# PCB_Board4_schematic_2_instrument_droid.net
KiCad netlist of a schematic drawn in Altium Designer
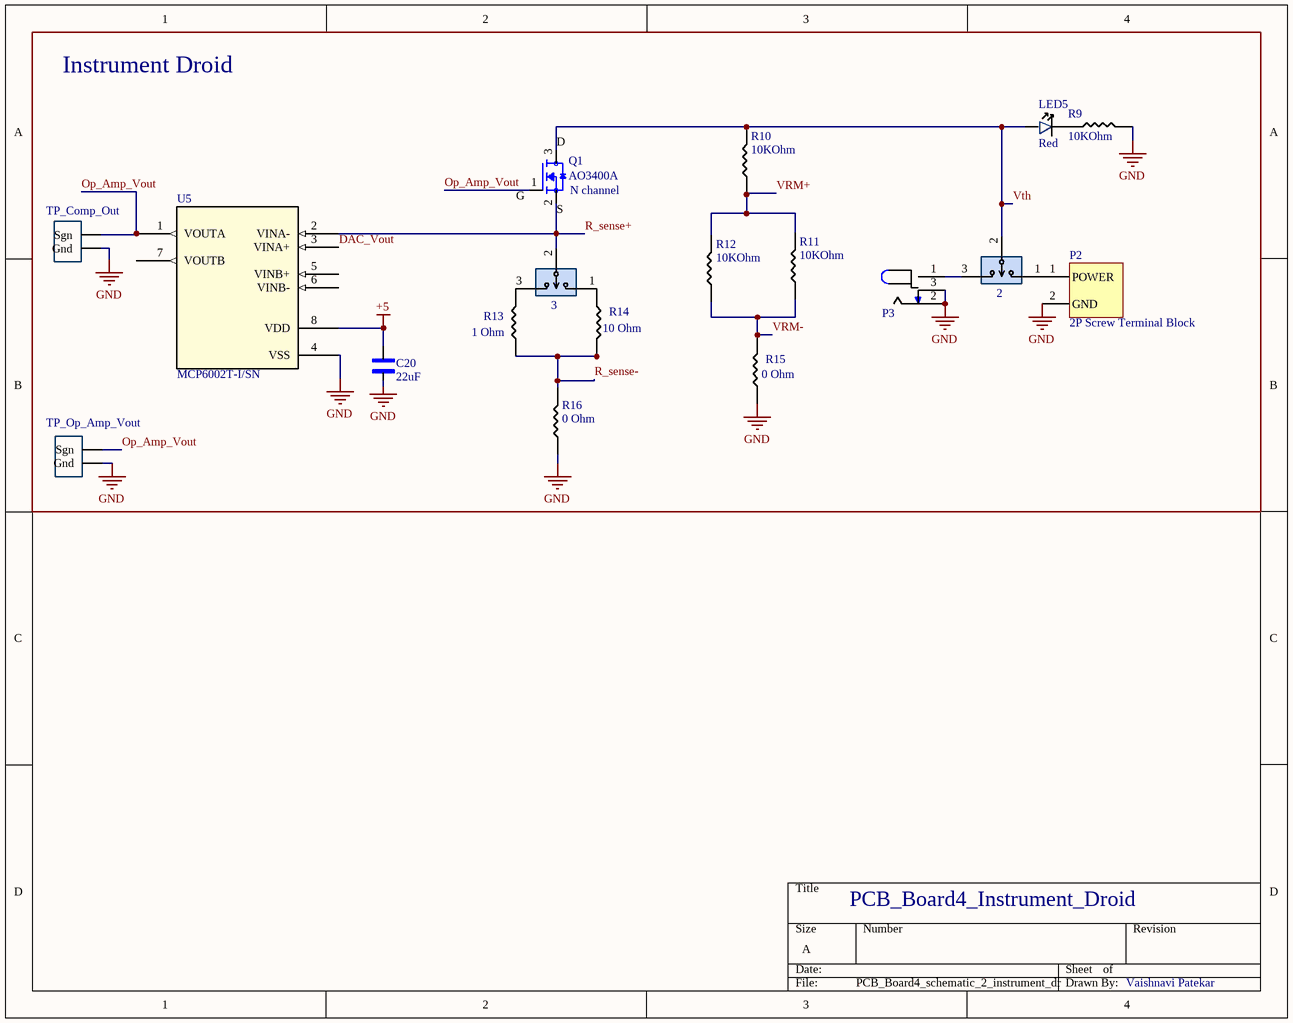
[diagram p0: PCB_Board4_schematic_2_instrument_droid.SchDoc]

(export (version "E")
  (design (tool "Eeschema 10.0.6"))
  (components
    (comp (ref "2")
      (value "PREC003SAAN-RC")
      (footprint "3_PIN_100mil")
      (description "Connector Header Through Hole 3 position 0.100\" (2.54mm)")
      (fields (field (name "LCSC PART#") "C49257"))
      (libsource (lib "ECEN5730Lib_2023_01_DS") (part "SW_3Pin_100mil_Switch"))
    )
    (comp (ref "3")
      (value "PREC003SAAN-RC")
      (footprint "3_PIN_100mil")
      (description "Connector Header Through Hole 3 position 0.100\" (2.54mm)")
      (fields (field (name "LCSC PART#") "C49257"))
      (libsource (lib "ECEN5730Lib_2023_01_DS") (part "SW_3Pin_100mil_Switch"))
    )
    (comp (ref "C20")
      (value "22uF")
      (footprint "1206_Passive_Capacitor")
      (description "22uF ±10% 25V X5R 1206 Multilayer Ceramic Capacitors MLCC - SMD/SMT RoHS")
      (fields (field (name "MFR PART #") "CL31A226KAHNNNE") (field (name "LCSC PART#") "C12891"))
      (libsource (lib "ECEN5730Lib_2023_01_DS") (part "C_22uF_1206"))
    )
    (comp (ref "LED5")
      (value "Red")
      (footprint "LED_1206")
      (description "Red 621~631nm 1206 Light Emitting Diodes (LED) RoHS")
      (fields (field (name "MFR PART #") "15-21/R6C-FQ1R1B/2T") (field (name "LCSC PART#") "C93133"))
      (libsource (lib "ECEN5730Lib_2023_01_DS") (part "LED_RED_1206"))
    )
    (comp (ref "P2")
      (value "2P Screw Terminal Block")
      (footprint "P_Terminal block 3.5mm-pitch")
      (description "Green Straight pin 3.5mm  pitch; P=3.5mm  Screw terminal ROHS")
      (fields (field (name "MFR PART #") "KF350-3.5-2P") (field (name "MANUFACTURER") "Cixi Kefa Elec"))
      (libsource (lib "ECEN5730Lib_2023_01_DS") (part "P_Terminal block"))
    )
    (comp (ref "P3")
      (value "Power Jack")
      (footprint "Power_Jack")
      (description "Power Barrel Connector Jack 2.10mm ID (0.083\"), 5.50mm OD (0.217\") Through Hole, Right Angle")
      (fields (field (name "MFR PART #") "PJ-102A") (field (name "LCSC PART#") "C136744"))
      (libsource (lib "ECEN5730Lib_2023_01_DS") (part "P_Power Jack"))
    )
    (comp (ref "Q1")
      (value "AO3400A")
      (footprint "N-MOSFET")
      (description "MOSFET N Trench 30V 5.7A 1.5V @ 250uA 26.5 m? @ 5.7A,10V SOT-23-3L RoHS")
      (fields (field (name "LCSC PART#") "C20917") (field (name "ALTIUM_VALUE") "N channel"))
      (libsource (lib "ECEN5730Lib_2023_01_DS") (part "Q_Nch_MOSFET"))
    )
    (comp (ref "R9")
      (value "10KOhm")
      (footprint "1206_Passive_Resitor")
      (description "10 kOhms ±5% 0.25W, 1/4W Chip Resistor 1206 (3216 Metric) Automotive AEC-Q200 Thick Film")
      (fields (field (name "MFR PART #") "RMCF1206FT10K0") (field (name "LCSC PART#") "C17902"))
      (libsource (lib "ECEN5730Lib_2023_01_DS") (part "R_10KOhm_1206"))
    )
    (comp (ref "R10")
      (value "10KOhm")
      (footprint "1206_Passive_Resitor")
      (description "10 kOhms ±5% 0.25W, 1/4W Chip Resistor 1206 (3216 Metric) Automotive AEC-Q200 Thick Film")
      (fields (field (name "MFR PART #") "RMCF1206FT10K0") (field (name "LCSC PART#") "C17902"))
      (libsource (lib "ECEN5730Lib_2023_01_DS") (part "R_10KOhm_1206"))
    )
    (comp (ref "R11")
      (value "10KOhm")
      (footprint "1206_Passive_Resitor")
      (description "10 kOhms ±5% 0.25W, 1/4W Chip Resistor 1206 (3216 Metric) Automotive AEC-Q200 Thick Film")
      (fields (field (name "MFR PART #") "RMCF1206FT10K0") (field (name "LCSC PART#") "C17902"))
      (libsource (lib "ECEN5730Lib_2023_01_DS") (part "R_10KOhm_1206"))
    )
    (comp (ref "R12")
      (value "10KOhm")
      (footprint "1206_Passive_Resitor")
      (description "10 kOhms ±5% 0.25W, 1/4W Chip Resistor 1206 (3216 Metric) Automotive AEC-Q200 Thick Film")
      (fields (field (name "MFR PART #") "RMCF1206FT10K0") (field (name "LCSC PART#") "C17902"))
      (libsource (lib "ECEN5730Lib_2023_01_DS") (part "R_10KOhm_1206"))
    )
    (comp (ref "R13")
      (value "1 Ohm")
      (footprint "1206_Passive_Resitor")
      (description "1Ω ±5% 0.25W ±400ppm/℃ 1206 Chip Resistor - Surface Mount RoHS")
      (fields (field (name "LCSC PART#") "C1409") (field (name "MFR PART #") "1206W4J010JT5E"))
      (libsource (lib "ECEN5730Lib_2023_01_DS") (part "R_1Ohm_1206"))
    )
    (comp (ref "R14")
      (value "10 Ohm")
      (footprint "1206_Passive_Resitor")
      (description "CHIP RESISTOR - SURFACE MOUNT 0.1OHMS ±1% 1/4W 1206 ROHS")
      (fields (field (name "MFR PART #") "1206W4F100JT5E") (field (name "LCSC PART#") "C17903"))
      (libsource (lib "ECEN5730Lib_2023_01_DS") (part "R_10Ohm_1206"))
    )
    (comp (ref "R15")
      (value "0 Ohm")
      (footprint "1206_Passive_Resitor")
      (description "CHIP RESISTOR - SURFACE MOUNT 0OHMS ±1% 1/4W 1206 ROHS")
      (fields (field (name "MFR PART #") "1206W4F0000T5E") (field (name "LCSC PART#") "C17888"))
      (libsource (lib "ECEN5730Lib_2023_01_DS") (part "R_0Ohm_1206"))
    )
    (comp (ref "R16")
      (value "0 Ohm")
      (footprint "1206_Passive_Resitor")
      (description "CHIP RESISTOR - SURFACE MOUNT 0OHMS ±1% 1/4W 1206 ROHS")
      (fields (field (name "MFR PART #") "1206W4F0000T5E") (field (name "LCSC PART#") "C17888"))
      (libsource (lib "ECEN5730Lib_2023_01_DS") (part "R_0Ohm_1206"))
    )
    (comp (ref "TP14")
      (value "TP_Comp_Out")
      (footprint "TP10x_Probe")
      (description "Test Point 300 mil centers")
      (libsource (lib "ECEN5730Lib_2023_01_DS") (part "TP_10x_Probe"))
    )
    (comp (ref "TP15")
      (value "TP_Op_Amp_Vout")
      (footprint "TP10x_Probe")
      (description "Test Point 300 mil centers")
      (libsource (lib "ECEN5730Lib_2023_01_DS") (part "TP_10x_Probe"))
    )
    (comp (ref "U5")
      (value "MCP6002T-I/SN")
      (footprint "SOIC127P600X175-8N")
      (description "0.6 V/us 2 1MHz 1.8V ~ 6V 100μA General Purpose SOIC-8_150mil  Operational Amplifier ROHS")
      (fields (field (name "MFR") "Microchip") (field (name "LCSC PART#") "C7377"))
      (libsource (lib "ECEN5730Lib_2023_01_DS") (part "U_MCP6002T-I/SN"))
    )
  )
  (nets
    (net (code "1") (name "+5") (class "Default")
      (node (ref "C20") (pin "1") (pinfunction "1_1") (pintype "passive"))
      (node (ref "U5") (pin "8") (pinfunction "VDD_8") (pintype "passive"))
    )
    (net (code "2") (name "/DAC_Vout") (class "Default")
      (node (ref "U5") (pin "3") (pinfunction "VINA+_3") (pintype "input"))
    )
    (net (code "3") (name "/Op_Amp_Vout") (class "Default")
      (node (ref "Q1") (pin "1") (pinfunction "G_1") (pintype "passive"))
      (node (ref "TP14") (pin "1") (pinfunction "Sgn_1") (pintype "passive"))
      (node (ref "TP15") (pin "1") (pinfunction "Sgn_1") (pintype "passive"))
      (node (ref "U5") (pin "1") (pinfunction "VOUTA_1") (pintype "output"))
    )
    (net (code "4") (name "/R_sense+") (class "Default")
      (node (ref "3") (pin "2") (pinfunction "2_2") (pintype "passive"))
      (node (ref "Q1") (pin "2") (pinfunction "S_2") (pintype "passive"))
      (node (ref "U5") (pin "2") (pinfunction "VINA-_2") (pintype "input"))
    )
    (net (code "5") (name "/R_sense-") (class "Default")
      (node (ref "R13") (pin "1") (pinfunction "1_1") (pintype "passive"))
      (node (ref "R14") (pin "2") (pinfunction "2_2") (pintype "passive"))
      (node (ref "R16") (pin "2") (pinfunction "2_2") (pintype "passive"))
    )
    (net (code "6") (name "/VRM+") (class "Default")
      (node (ref "R10") (pin "1") (pinfunction "1_1") (pintype "passive"))
      (node (ref "R11") (pin "2") (pinfunction "2_2") (pintype "passive"))
      (node (ref "R12") (pin "2") (pinfunction "2_2") (pintype "passive"))
    )
    (net (code "7") (name "/VRM-") (class "Default")
      (node (ref "R11") (pin "1") (pinfunction "1_1") (pintype "passive"))
      (node (ref "R12") (pin "1") (pinfunction "1_1") (pintype "passive"))
      (node (ref "R15") (pin "2") (pinfunction "2_2") (pintype "passive"))
    )
    (net (code "8") (name "/Vth") (class "Default")
      (node (ref "2") (pin "2") (pinfunction "2_2") (pintype "passive"))
      (node (ref "LED5") (pin "1") (pinfunction "1_1") (pintype "passive"))
      (node (ref "Q1") (pin "3") (pinfunction "D_3") (pintype "passive"))
      (node (ref "R10") (pin "2") (pinfunction "2_2") (pintype "passive"))
    )
    (net (code "9") (name "GND") (class "Default")
      (node (ref "C20") (pin "2") (pinfunction "2_2") (pintype "passive"))
      (node (ref "P2") (pin "2") (pinfunction "GND_2") (pintype "passive"))
      (node (ref "P3") (pin "2") (pinfunction "2_2") (pintype "power_in"))
      (node (ref "P3") (pin "3") (pinfunction "3_3") (pintype "power_in"))
      (node (ref "R15") (pin "1") (pinfunction "1_1") (pintype "passive"))
      (node (ref "R16") (pin "1") (pinfunction "1_1") (pintype "passive"))
      (node (ref "R9") (pin "2") (pinfunction "2_2") (pintype "passive"))
      (node (ref "TP14") (pin "2") (pinfunction "Gnd_2") (pintype "passive"))
      (node (ref "TP15") (pin "2") (pinfunction "Gnd_2") (pintype "passive"))
      (node (ref "U5") (pin "4") (pinfunction "VSS_4") (pintype "passive"))
    )
    (net (code "10") (name "Net-(2-Pad3)") (class "Default")
      (node (ref "2") (pin "3") (pinfunction "3_3") (pintype "passive"))
      (node (ref "P3") (pin "1") (pinfunction "1_1") (pintype "power_in"))
    )
    (net (code "11") (name "Net-(3-Pad1)") (class "Default")
      (node (ref "3") (pin "1") (pinfunction "1_1") (pintype "passive"))
      (node (ref "R14") (pin "1") (pinfunction "1_1") (pintype "passive"))
    )
    (net (code "12") (name "Net-(3-Pad3)") (class "Default")
      (node (ref "3") (pin "3") (pinfunction "3_3") (pintype "passive"))
      (node (ref "R13") (pin "2") (pinfunction "2_2") (pintype "passive"))
    )
    (net (code "13") (name "Net-(LED5-Pad2)") (class "Default")
      (node (ref "LED5") (pin "2") (pinfunction "2_2") (pintype "passive"))
      (node (ref "R9") (pin "1") (pinfunction "1_1") (pintype "passive"))
    )
    (net (code "14") (name "Net-(P2-POWER)") (class "Default")
      (node (ref "2") (pin "1") (pinfunction "1_1") (pintype "passive"))
      (node (ref "P2") (pin "1") (pinfunction "POWER_1") (pintype "passive"))
    )
    (net (code "15") (name "unconnected-(U5-VINB+-Pad5)") (class "Default")
      (node (ref "U5") (pin "5") (pinfunction "VINB+_5") (pintype "input"))
    )
    (net (code "16") (name "unconnected-(U5-VINB--Pad6)") (class "Default")
      (node (ref "U5") (pin "6") (pinfunction "VINB-_6") (pintype "input"))
    )
    (net (code "17") (name "unconnected-(U5-VOUTB-Pad7)") (class "Default")
      (node (ref "U5") (pin "7") (pinfunction "VOUTB_7") (pintype "output"))
    )
  )
)
